# pca10028_power_supply.net
KiCad netlist of a schematic drawn in Altium Designer
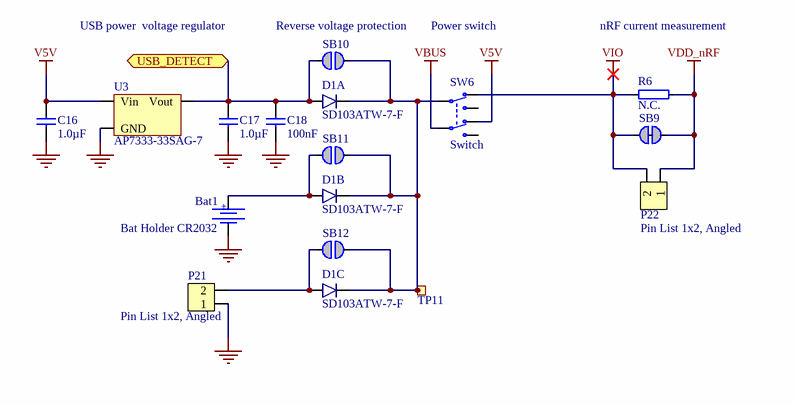
[diagram p0: pca10028_power_supply.SchDoc]

(export (version "E")
  (design (tool "Eeschema 10.0.6"))
  (components
    (comp (ref "Bat1")
      (value "Bat Holder CR2032")
      (footprint "CR2032_HOLDER_SMD")
      (description "Bat Holder CR2032 SMD")
      (fields
        (field (name "MANUFACTURER") "Keystone")
        (field (name "MANUFACTURER PART NUMBER") "3002")
        (field (name "PUBLISHER") "Nordic Semiconductor")
      )
      (libsource (lib "Nordic Passive DB") (part "Battery"))
    )
    (comp (ref "C16")
      (value "1.0µF")
      (footprint "CAPC1608X06L")
      (description "Capacitor, X7R, ±10%")
      (fields (field (name "PART NUMBER") "C0603-1µ0") (field (name "PUBLISHER") "Nordic Semiconductor"))
      (libsource (lib "Nordic Passive DB") (part "CAP"))
    )
    (comp (ref "C17")
      (value "1.0µF")
      (footprint "CAPC1608X06L")
      (description "Capacitor, X7R, ±10%")
      (fields (field (name "PART NUMBER") "C0603-1µ0") (field (name "PUBLISHER") "Nordic Semiconductor"))
      (libsource (lib "Nordic Passive DB") (part "CAP"))
    )
    (comp (ref "C18")
      (value "100nF")
      (footprint "CAPC1005X04L")
      (description "Capacitor, X7R, ±10%")
      (fields (field (name "PART NUMBER") "C0402-100n") (field (name "PUBLISHER") "Nordic Semiconductor"))
      (libsource (lib "Nordic Passive DB") (part "CAP"))
    )
    (comp (ref "D1")
      (value "SD103ATW-7-F")
      (footprint "SOT-363")
      (description "Surface Mount Schottky Barrier Diode Array")
      (fields
        (field (name "MANUFACTURER") "Diodes Incorporated")
        (field (name "2ND SOURCE PART NUMBER") "177-3507")
        (field (name "PUBLISHER") "Nordic Semiconductor")
      )
      (libsource (lib "Nordic Discrete DB") (part "D{colon}DIODE_3_IND"))
    )
    (comp (ref "P21")
      (value "Pin List 1x2, Angled")
      (footprint "LIST_ANG_1x2-SMD-2.54MM")
      (description "Pin List 1x2, 2.54mm (100mil), Right Angled, SMD")
      (fields
        (field (name "PART NUMBER") "Pin List Ang 1x2 SMD, 2.54mm")
        (field (name "2ND SOURCE PART NUMBER") "S1113E-02-ND")
        (field (name "PUBLISHER") "Nordic Semiconductor")
      )
      (libsource (lib "Nordic Passive DB") (part "CONN-2"))
    )
    (comp (ref "P22")
      (value "Pin List 1x2, Angled")
      (footprint "LIST_ANG_1x2-SMD-2.54MM")
      (description "Pin List 1x2, 2.54mm (100mil), Right Angled, SMD")
      (fields
        (field (name "PART NUMBER") "Pin List Ang 1x2 SMD, 2.54mm")
        (field (name "2ND SOURCE PART NUMBER") "S1113E-02-ND")
        (field (name "PUBLISHER") "Nordic Semiconductor")
      )
      (libsource (lib "") (part "CONN-2_1"))
    )
    (comp (ref "R6")
      (value "N.C.")
      (footprint "RESC1005X04L")
      (description "Not mounted")
      (fields (field (name "PART NUMBER") "R0402-N.C.") (field (name "PUBLISHER") "Nordic Semiconductor"))
      (libsource (lib "Nordic Passive DB") (part "RES_1"))
    )
    (comp (ref "SB9")
      (value "Solderbridge")
      (footprint "Solderbridge_Shorted")
      (description "Shorted Solderbridge")
      (fields
        (field (name "PART NUMBER") "Solderbridge Shorted")
        (field (name "PUBLISHER") "Nordic Semiconductor")
      )
      (libsource (lib "Nordic Passive DB") (part "SOLDERBRIDGE_SHORTED"))
    )
    (comp (ref "SB10")
      (value "Solderbridge")
      (footprint "Solderbridge")
      (fields (field (name "PUBLISHER") "Nordic Semiconductor"))
      (libsource (lib "Nordic Passive DB") (part "SOLDERBRIDGE"))
    )
    (comp (ref "SB11")
      (value "Solderbridge")
      (footprint "Solderbridge")
      (fields (field (name "PUBLISHER") "Nordic Semiconductor"))
      (libsource (lib "Nordic Passive DB") (part "SOLDERBRIDGE"))
    )
    (comp (ref "SB12")
      (value "Solderbridge")
      (footprint "Solderbridge")
      (fields (field (name "PUBLISHER") "Nordic Semiconductor"))
      (libsource (lib "Nordic Passive DB") (part "SOLDERBRIDGE"))
    )
    (comp (ref "SW6")
      (value "Switch")
      (footprint "JS202011SCQN")
      (description "SMD slide Switch (ON-ON)")
      (fields
        (field (name "PART NUMBER") "JS202011SCQN")
        (field (name "MANUFACTURER") "C&K Components")
        (field (name "PUBLISHER") "Nordic Semiconductor")
      )
      (libsource (lib "Nordic Discrete DB") (part "SW-DPDT"))
    )
    (comp (ref "TP11")
      (value "Ø1.0mm,SMD")
      (footprint "TP_SMD_Ø1.0mm")
      (description "1.0mm circular SMD testpad")
      (fields
        (field (name "PART NUMBER") "TP_SMD_Ø1.0MM")
        (field (name "MANUFACTURER") "Nordic Semiconductor")
        (field (name "PUBLISHER") "Nordic Semiconductor")
      )
      (libsource (lib "Nordic Passive DB") (part "TESTPAD"))
    )
    (comp (ref "U3")
      (value "AP7333-33SAG-7")
      (footprint "SOT-23A")
      (description "300mA, Low Quiescent Current, Fast Transient Low Dropout Linear Regulator")
      (fields
        (field (name "MANUFACTURER") "Diodes Incorporated")
        (field (name "PUBLISHER") "Nordic Semiconductor")
      )
      (libsource (lib "Nordic Active DB") (part "AP7333-XXSAG"))
    )
  )
  (nets
    (net (code "1") (name "/USB_DETECT") (class "Default")
      (node (ref "C17") (pin "2") (pinfunction "2_2") (pintype "passive"))
      (node (ref "C18") (pin "2") (pinfunction "2_2") (pintype "passive"))
      (node (ref "D1") (pin "6") (pinfunction "A1_6") (pintype "passive"))
      (node (ref "SB10") (pin "2") (pinfunction "1_2") (pintype "passive"))
      (node (ref "U3") (pin "2") (pinfunction "Vout_2") (pintype "passive"))
    )
    (net (code "2") (name "GND") (class "Default")
      (node (ref "Bat1") (pin "2") (pintype "passive"))
      (node (ref "C16") (pin "1") (pinfunction "1_1") (pintype "passive"))
      (node (ref "C17") (pin "1") (pinfunction "1_1") (pintype "passive"))
      (node (ref "C18") (pin "1") (pinfunction "1_1") (pintype "passive"))
      (node (ref "P21") (pin "1") (pinfunction "1_1") (pintype "passive"))
      (node (ref "U3") (pin "3") (pinfunction "GND_3") (pintype "passive"))
    )
    (net (code "3") (name "Net-(D1A-C1)") (class "Default")
      (node (ref "D1") (pin "1") (pinfunction "C1_1") (pintype "passive"))
      (node (ref "D1") (pin "2") (pinfunction "C2_2") (pintype "passive"))
      (node (ref "D1") (pin "3") (pinfunction "C3_3") (pintype "passive"))
      (node (ref "SB10") (pin "1") (pinfunction "0_1") (pintype "passive"))
      (node (ref "SB11") (pin "1") (pinfunction "0_1") (pintype "passive"))
      (node (ref "SB12") (pin "1") (pinfunction "0_1") (pintype "passive"))
      (node (ref "SW6") (pin "2") (pinfunction "COM-1_2") (pintype "passive"))
      (node (ref "TP11") (pin "1") (pinfunction "1_1") (pintype "passive"))
    )
    (net (code "4") (name "Net-(D1B-A2)") (class "Default")
      (node (ref "Bat1") (pin "1") (pintype "passive"))
      (node (ref "D1") (pin "5") (pinfunction "A2_5") (pintype "passive"))
      (node (ref "SB11") (pin "2") (pinfunction "1_2") (pintype "passive"))
    )
    (net (code "5") (name "Net-(D1C-A3)") (class "Default")
      (node (ref "D1") (pin "4") (pinfunction "A3_4") (pintype "passive"))
      (node (ref "P21") (pin "2") (pinfunction "2_2") (pintype "passive"))
      (node (ref "SB12") (pin "2") (pinfunction "1_2") (pintype "passive"))
    )
    (net (code "6") (name "V5V") (class "Default")
      (node (ref "C16") (pin "2") (pinfunction "2_2") (pintype "passive"))
      (node (ref "SW6") (pin "6") (pinfunction "N.C-2_6") (pintype "passive"))
      (node (ref "U3") (pin "1") (pinfunction "Vin_1") (pintype "passive"))
    )
    (net (code "7") (name "VBUS") (class "Default")
      (node (ref "SW6") (pin "5") (pinfunction "COM-2_5") (pintype "passive"))
    )
    (net (code "8") (name "VDD_nRF") (class "Default")
      (node (ref "P22") (pin "1") (pinfunction "1_1") (pintype "passive"))
      (node (ref "R6") (pin "2") (pinfunction "2_2") (pintype "passive"))
      (node (ref "SB9") (pin "1") (pinfunction "0_1") (pintype "passive"))
    )
    (net (code "9") (name "VIO") (class "Default")
      (node (ref "P22") (pin "2") (pinfunction "2_2") (pintype "passive"))
      (node (ref "R6") (pin "1") (pinfunction "1_1") (pintype "passive"))
      (node (ref "SB9") (pin "2") (pinfunction "1_2") (pintype "passive"))
      (node (ref "SW6") (pin "3") (pinfunction "N.C-1_3") (pintype "passive"))
    )
    (net (code "10") (name "unconnected-(SW6-N.O-1-Pad1)") (class "Default")
      (node (ref "SW6") (pin "1") (pinfunction "N.O-1_1") (pintype "passive"))
    )
    (net (code "11") (name "unconnected-(SW6-N.O-2-Pad4)") (class "Default")
      (node (ref "SW6") (pin "4") (pinfunction "N.O-2_4") (pintype "passive"))
    )
  )
)
